# Atom_Multiout_Main.net
KiCad netlist of a schematic drawn in EAGLE
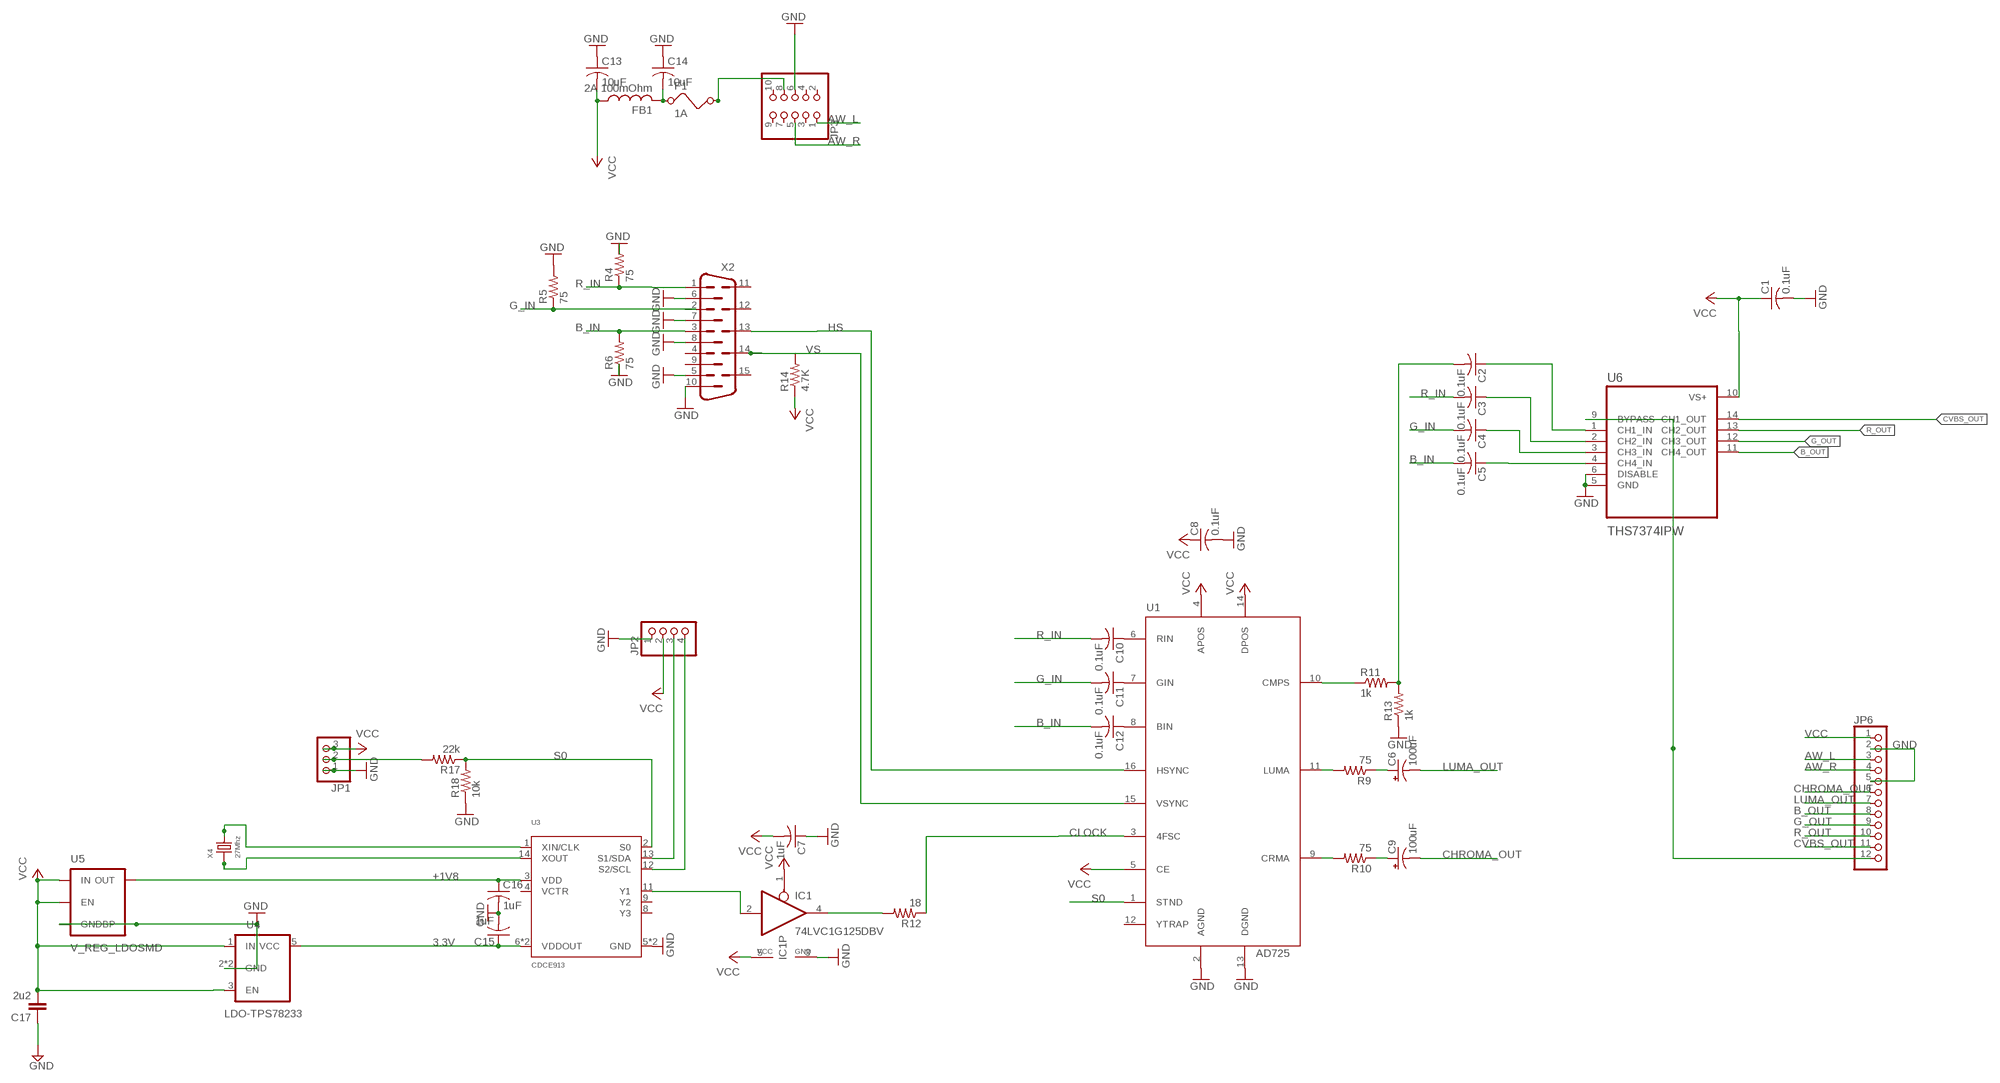
[diagram p0: schematic, sheet 1]

(export (version "E")
  (design (tool "Eeschema 10.0.6"))
  (components
    (comp (ref "C1")
      (value "0.1uF")
      (footprint "eagle-import:C0603@1")
      (libsource (lib "eagle-import") (part "C-USC0603"))
    )
    (comp (ref "C2")
      (value "0.1uF")
      (footprint "eagle-import:C0603@1")
      (libsource (lib "eagle-import") (part "C-USC0603"))
    )
    (comp (ref "C3")
      (value "0.1uF")
      (footprint "eagle-import:C0603@1")
      (libsource (lib "eagle-import") (part "C-USC0603"))
    )
    (comp (ref "C4")
      (value "0.1uF")
      (footprint "eagle-import:C0603@1")
      (libsource (lib "eagle-import") (part "C-USC0603"))
    )
    (comp (ref "C5")
      (value "0.1uF")
      (footprint "eagle-import:C0603@1")
      (libsource (lib "eagle-import") (part "C-USC0603"))
    )
    (comp (ref "C6")
      (value "100uF")
      (footprint "eagle-import:C_6032-28R")
      (libsource (lib "eagle-import") (part "CPOL-USC/6032-28R"))
    )
    (comp (ref "C7")
      (value "1uF")
      (footprint "eagle-import:C0603@1")
      (libsource (lib "eagle-import") (part "C-USC0603"))
    )
    (comp (ref "C8")
      (value "0.1uF")
      (footprint "eagle-import:C0603@1")
      (libsource (lib "eagle-import") (part "C-USC0603"))
    )
    (comp (ref "C9")
      (value "100uF")
      (footprint "eagle-import:C_6032-28R")
      (libsource (lib "eagle-import") (part "CPOL-USC/6032-28R"))
    )
    (comp (ref "C10")
      (value "0.1uF")
      (footprint "eagle-import:C0603@1")
      (libsource (lib "eagle-import") (part "C-USC0603"))
    )
    (comp (ref "C11")
      (value "0.1uF")
      (footprint "eagle-import:C0603@1")
      (libsource (lib "eagle-import") (part "C-USC0603"))
    )
    (comp (ref "C12")
      (value "0.1uF")
      (footprint "eagle-import:C0603@1")
      (libsource (lib "eagle-import") (part "C-USC0603"))
    )
    (comp (ref "C13")
      (value "10uF")
      (footprint "eagle-import:C0603@1")
      (libsource (lib "eagle-import") (part "C-USC0603"))
    )
    (comp (ref "C14")
      (value "10uF")
      (footprint "eagle-import:C0603@1")
      (libsource (lib "eagle-import") (part "C-USC0603"))
    )
    (comp (ref "C15")
      (value "1uF")
      (footprint "eagle-import:C0603@1")
      (libsource (lib "eagle-import") (part "C-USC0603"))
    )
    (comp (ref "C16")
      (value "1uF")
      (footprint "eagle-import:C0603@1")
      (libsource (lib "eagle-import") (part "C-USC0603"))
    )
    (comp (ref "C17")
      (value "2u2")
      (footprint "eagle-import:C0603")
      (libsource (lib "eagle-import") (part "C-EUC0603"))
    )
    (comp (ref "F1")
      (value "1A")
      (footprint "eagle-import:1812")
      (libsource (lib "eagle-import") (part "FUSEF"))
    )
    (comp (ref "FB1")
      (value "2A 100mOhm")
      (footprint "eagle-import:0805")
      (libsource (lib "eagle-import") (part "FERRITE-BEADB"))
    )
    (comp (ref "IC1")
      (value "74LVC1G125DBV")
      (footprint "eagle-import:SOT23-5")
      (libsource (lib "eagle-import") (part "741G125DBVLVC"))
    )
    (comp (ref "JP1")
      (value "PINHD-1X03_2.54-S")
      (footprint "eagle-import:1X03-S")
      (libsource (lib "eagle-import") (part "PINHD-1X03_2.54-S"))
    )
    (comp (ref "JP2")
      (value "PINHD-1X04_2.00")
      (footprint "eagle-import:1X04M")
      (libsource (lib "eagle-import") (part "PINHD-1X04_2.00"))
    )
    (comp (ref "JP3")
      (value "PINHD-2X05_2.00")
      (footprint "eagle-import:2X05M")
      (libsource (lib "eagle-import") (part "PINHD-2X05_2.00"))
    )
    (comp (ref "JP6")
      (value "PINHD-1X12_2.54-S")
      (footprint "eagle-import:1X12-S")
      (libsource (lib "eagle-import") (part "PINHD-1X12_2.54-S"))
    )
    (comp (ref "R4")
      (value "75")
      (footprint "eagle-import:R0603")
      (libsource (lib "eagle-import") (part "R-US_R0603"))
    )
    (comp (ref "R5")
      (value "75")
      (footprint "eagle-import:R0603")
      (libsource (lib "eagle-import") (part "R-US_R0603"))
    )
    (comp (ref "R6")
      (value "75")
      (footprint "eagle-import:R0603")
      (libsource (lib "eagle-import") (part "R-US_R0603"))
    )
    (comp (ref "R9")
      (value "75")
      (footprint "eagle-import:R0603")
      (libsource (lib "eagle-import") (part "R-US_R0603"))
    )
    (comp (ref "R10")
      (value "75")
      (footprint "eagle-import:R0603")
      (libsource (lib "eagle-import") (part "R-US_R0603"))
    )
    (comp (ref "R11")
      (value "1k")
      (footprint "eagle-import:R0603")
      (libsource (lib "eagle-import") (part "R-US_R0603"))
    )
    (comp (ref "R12")
      (value "18")
      (footprint "eagle-import:R0603")
      (libsource (lib "eagle-import") (part "R-US_R0603"))
    )
    (comp (ref "R13")
      (value "1k")
      (footprint "eagle-import:R0603")
      (libsource (lib "eagle-import") (part "R-US_R0603"))
    )
    (comp (ref "R14")
      (value "4.7K")
      (footprint "eagle-import:R0603")
      (libsource (lib "eagle-import") (part "R-US_R0603"))
    )
    (comp (ref "R17")
      (value "22k")
      (footprint "eagle-import:R0603")
      (libsource (lib "eagle-import") (part "R-US_R0603"))
    )
    (comp (ref "R18")
      (value "10k")
      (footprint "eagle-import:R0603")
      (libsource (lib "eagle-import") (part "R-US_R0603"))
    )
    (comp (ref "U1")
      (value "AD725")
      (footprint "eagle-import:SOIC16W")
      (libsource (lib "eagle-import") (part "AD725"))
    )
    (comp (ref "U3")
      (value "CDCE913")
      (footprint "eagle-import:TSSOP14")
      (libsource (lib "eagle-import") (part "CDCE913"))
    )
    (comp (ref "U4")
      (value "LDO-TPS78233")
      (footprint "eagle-import:SOT23-5")
      (libsource (lib "eagle-import") (part "LDO-TPS78233"))
    )
    (comp (ref "U5")
      (value "V_REG_LDOSMD")
      (footprint "eagle-import:SOT23-5")
      (libsource (lib "eagle-import") (part "V_REG_LDOSMD"))
    )
    (comp (ref "U6")
      (value "THS7374IPW")
      (footprint "eagle-import:SOP65P640X120-14N")
      (fields (field (name "MF") "Texas Instruments"))
      (libsource (lib "eagle-import") (part "THS7374IPW"))
    )
    (comp (ref "X2")
      (value "HM15V")
      (footprint "eagle-import:HDM15V")
      (libsource (lib "eagle-import") (part "HM15V"))
    )
    (comp (ref "X4")
      (value "27Mhz")
      (footprint "eagle-import:X2-SMD-5.0X3.2X1.3MM")
      (libsource (lib "eagle-import") (part "CRYSTAL'5032'"))
    )
  )
  (nets
    (net (code "1") (name "/+1V8") (class "Default")
      (node (ref "C16") (pin "1") (pinfunction "1_1") (pintype "passive"))
      (node (ref "U3") (pin "3") (pinfunction "VDD_3") (pintype "bidirectional"))
      (node (ref "U5") (pin "5") (pinfunction "OUT_5") (pintype "passive"))
    )
    (net (code "2") (name "/3.3V") (class "Default")
      (node (ref "C15") (pin "1") (pinfunction "1_1") (pintype "passive"))
      (node (ref "U3") (pin "6") (pinfunction "VDDOUT_6") (pintype "bidirectional"))
      (node (ref "U3") (pin "7") (pinfunction "VDDOUT_7") (pintype "bidirectional"))
      (node (ref "U4") (pin "5") (pinfunction "VCC_5") (pintype "power_in"))
    )
    (net (code "3") (name "/AW_L") (class "Default")
      (node (ref "JP3") (pin "1") (pinfunction "1_1") (pintype "passive"))
      (node (ref "JP6") (pin "3") (pinfunction "3_3") (pintype "passive"))
    )
    (net (code "4") (name "/AW_R") (class "Default")
      (node (ref "JP3") (pin "5") (pinfunction "5_5") (pintype "passive"))
      (node (ref "JP6") (pin "4") (pinfunction "4_4") (pintype "passive"))
    )
    (net (code "5") (name "/B_IN") (class "Default")
      (node (ref "C12") (pin "2") (pinfunction "2_2") (pintype "passive"))
      (node (ref "C5") (pin "2") (pinfunction "2_2") (pintype "passive"))
      (node (ref "R6") (pin "2") (pinfunction "2_2") (pintype "passive"))
      (node (ref "X2") (pin "3") (pinfunction "3_3") (pintype "passive"))
    )
    (net (code "6") (name "/CHROMA_OUT") (class "Default")
      (node (ref "C9") (pin "-") (pinfunction "-_-") (pintype "passive"))
      (node (ref "JP6") (pin "6") (pinfunction "6_6") (pintype "passive"))
    )
    (net (code "7") (name "/CLOCK") (class "Default")
      (node (ref "R12") (pin "1") (pinfunction "1_1") (pintype "passive"))
      (node (ref "U1") (pin "3") (pinfunction "4FSC_3") (pintype "input"))
    )
    (net (code "8") (name "/G_IN") (class "Default")
      (node (ref "C11") (pin "2") (pinfunction "2_2") (pintype "passive"))
      (node (ref "C4") (pin "2") (pinfunction "2_2") (pintype "passive"))
      (node (ref "R5") (pin "1") (pinfunction "1_1") (pintype "passive"))
      (node (ref "X2") (pin "2") (pinfunction "2_2") (pintype "passive"))
    )
    (net (code "9") (name "/HS") (class "Default")
      (node (ref "U1") (pin "16") (pinfunction "HSYNC_16") (pintype "input"))
      (node (ref "X2") (pin "13") (pinfunction "13_13") (pintype "passive"))
    )
    (net (code "10") (name "/LUMA_OUT") (class "Default")
      (node (ref "C6") (pin "-") (pinfunction "-_-") (pintype "passive"))
      (node (ref "JP6") (pin "7") (pinfunction "7_7") (pintype "passive"))
    )
    (net (code "11") (name "/R_IN") (class "Default")
      (node (ref "C10") (pin "2") (pinfunction "2_2") (pintype "passive"))
      (node (ref "C3") (pin "2") (pinfunction "2_2") (pintype "passive"))
      (node (ref "R4") (pin "1") (pinfunction "1_1") (pintype "passive"))
      (node (ref "X2") (pin "1") (pinfunction "1_1") (pintype "passive"))
    )
    (net (code "12") (name "/S0") (class "Default")
      (node (ref "R17") (pin "1") (pinfunction "1_1") (pintype "passive"))
      (node (ref "R18") (pin "2") (pinfunction "2_2") (pintype "passive"))
      (node (ref "U1") (pin "1") (pinfunction "STND_1") (pintype "input"))
      (node (ref "U3") (pin "2") (pinfunction "S0_2") (pintype "bidirectional"))
    )
    (net (code "13") (name "/VS") (class "Default")
      (node (ref "R14") (pin "2") (pinfunction "2_2") (pintype "passive"))
      (node (ref "U1") (pin "15") (pinfunction "VSYNC_15") (pintype "input"))
      (node (ref "X2") (pin "14") (pinfunction "14_14") (pintype "passive"))
    )
    (net (code "14") (name "B_OUT") (class "Default")
      (node (ref "JP6") (pin "8") (pinfunction "8_8") (pintype "passive"))
      (node (ref "U6") (pin "11") (pinfunction "CH4_OUT_11") (pintype "output"))
    )
    (net (code "15") (name "CVBS_OUT") (class "Default")
      (node (ref "JP6") (pin "11") (pinfunction "11_11") (pintype "passive"))
      (node (ref "U6") (pin "14") (pinfunction "CH1_OUT_14") (pintype "output"))
    )
    (net (code "16") (name "GND") (class "Default")
      (node (ref "C1") (pin "2") (pinfunction "2_2") (pintype "passive"))
      (node (ref "C13") (pin "1") (pinfunction "1_1") (pintype "passive"))
      (node (ref "C14") (pin "1") (pinfunction "1_1") (pintype "passive"))
      (node (ref "C15") (pin "2") (pinfunction "2_2") (pintype "passive"))
      (node (ref "C16") (pin "2") (pinfunction "2_2") (pintype "passive"))
      (node (ref "C17") (pin "1") (pinfunction "1_1") (pintype "passive"))
      (node (ref "C7") (pin "1") (pinfunction "1_1") (pintype "passive"))
      (node (ref "C8") (pin "2") (pinfunction "2_2") (pintype "passive"))
      (node (ref "IC1") (pin "3") (pinfunction "GND_3") (pintype "power_in"))
      (node (ref "JP1") (pin "1") (pinfunction "1_1") (pintype "passive"))
      (node (ref "JP2") (pin "1") (pinfunction "1_1") (pintype "passive"))
      (node (ref "JP3") (pin "6") (pinfunction "6_6") (pintype "passive"))
      (node (ref "JP6") (pin "2") (pinfunction "2_2") (pintype "passive"))
      (node (ref "JP6") (pin "5") (pinfunction "5_5") (pintype "passive"))
      (node (ref "R13") (pin "1") (pinfunction "1_1") (pintype "passive"))
      (node (ref "R18") (pin "1") (pinfunction "1_1") (pintype "passive"))
      (node (ref "R4") (pin "2") (pinfunction "2_2") (pintype "passive"))
      (node (ref "R5") (pin "2") (pinfunction "2_2") (pintype "passive"))
      (node (ref "R6") (pin "1") (pinfunction "1_1") (pintype "passive"))
      (node (ref "U1") (pin "13") (pinfunction "DGND_13") (pintype "power_in"))
      (node (ref "U1") (pin "2") (pinfunction "AGND_2") (pintype "power_in"))
      (node (ref "U3") (pin "10") (pinfunction "GND_10") (pintype "bidirectional"))
      (node (ref "U3") (pin "5") (pinfunction "GND_5") (pintype "bidirectional"))
      (node (ref "U4") (pin "2") (pinfunction "GND_2") (pintype "input"))
      (node (ref "U4") (pin "4") (pinfunction "GND_4") (pintype "input"))
      (node (ref "U5") (pin "2") (pinfunction "GND_2") (pintype "input"))
      (node (ref "U5") (pin "4") (pinfunction "BP_4") (pintype "input"))
      (node (ref "U6") (pin "5") (pinfunction "GND_5") (pintype "input"))
      (node (ref "U6") (pin "6") (pinfunction "DISABLE_6") (pintype "input"))
      (node (ref "X2") (pin "10") (pinfunction "10_10") (pintype "passive"))
      (node (ref "X2") (pin "5") (pinfunction "5_5") (pintype "passive"))
      (node (ref "X2") (pin "6") (pinfunction "6_6") (pintype "passive"))
      (node (ref "X2") (pin "7") (pinfunction "7_7") (pintype "passive"))
      (node (ref "X2") (pin "8") (pinfunction "8_8") (pintype "passive"))
    )
    (net (code "17") (name "G_OUT") (class "Default")
      (node (ref "JP6") (pin "9") (pinfunction "9_9") (pintype "passive"))
      (node (ref "U6") (pin "12") (pinfunction "CH3_OUT_12") (pintype "output"))
    )
    (net (code "18") (name "Net-(C2-Pad2)") (class "Default")
      (node (ref "C2") (pin "2") (pinfunction "2_2") (pintype "passive"))
      (node (ref "R11") (pin "2") (pinfunction "2_2") (pintype "passive"))
      (node (ref "R13") (pin "2") (pinfunction "2_2") (pintype "passive"))
    )
    (net (code "19") (name "Net-(C6-Pad+)") (class "Default")
      (node (ref "C6") (pin "+") (pinfunction "+_+") (pintype "passive"))
      (node (ref "R9") (pin "1") (pinfunction "1_1") (pintype "passive"))
    )
    (net (code "20") (name "Net-(C9-Pad+)") (class "Default")
      (node (ref "C9") (pin "+") (pinfunction "+_+") (pintype "passive"))
      (node (ref "R10") (pin "1") (pinfunction "1_1") (pintype "passive"))
    )
    (net (code "21") (name "Net-(C14-Pad2)") (class "Default")
      (node (ref "C14") (pin "2") (pinfunction "2_2") (pintype "passive"))
      (node (ref "F1") (pin "1") (pinfunction "1_1") (pintype "passive"))
      (node (ref "FB1") (pin "2") (pinfunction "2_2") (pintype "passive"))
    )
    (net (code "22") (name "Net-(F1-Pad2)") (class "Default")
      (node (ref "F1") (pin "2") (pinfunction "2_2") (pintype "passive"))
      (node (ref "JP3") (pin "8") (pinfunction "8_8") (pintype "passive"))
    )
    (net (code "23") (name "Net-(IC1A-I)") (class "Default")
      (node (ref "IC1") (pin "2") (pinfunction "I_2") (pintype "input"))
      (node (ref "U3") (pin "11") (pinfunction "Y1_11") (pintype "bidirectional"))
    )
    (net (code "24") (name "Net-(IC1A-O)") (class "Default")
      (node (ref "IC1") (pin "4") (pinfunction "O_4") (pintype "tri_state"))
      (node (ref "R12") (pin "2") (pinfunction "2_2") (pintype "passive"))
    )
    (net (code "25") (name "Net-(JP1-Pad2)") (class "Default")
      (node (ref "JP1") (pin "2") (pinfunction "2_2") (pintype "passive"))
      (node (ref "R17") (pin "2") (pinfunction "2_2") (pintype "passive"))
    )
    (net (code "26") (name "Net-(U1-BIN)") (class "Default")
      (node (ref "C12") (pin "1") (pinfunction "1_1") (pintype "passive"))
      (node (ref "U1") (pin "8") (pinfunction "BIN_8") (pintype "input"))
    )
    (net (code "27") (name "Net-(U1-CMPS)") (class "Default")
      (node (ref "R11") (pin "1") (pinfunction "1_1") (pintype "passive"))
      (node (ref "U1") (pin "10") (pinfunction "CMPS_10") (pintype "output"))
    )
    (net (code "28") (name "Net-(U1-CRMA)") (class "Default")
      (node (ref "R10") (pin "2") (pinfunction "2_2") (pintype "passive"))
      (node (ref "U1") (pin "9") (pinfunction "CRMA_9") (pintype "output"))
    )
    (net (code "29") (name "Net-(U1-GIN)") (class "Default")
      (node (ref "C11") (pin "1") (pinfunction "1_1") (pintype "passive"))
      (node (ref "U1") (pin "7") (pinfunction "GIN_7") (pintype "input"))
    )
    (net (code "30") (name "Net-(U1-LUMA)") (class "Default")
      (node (ref "R9") (pin "2") (pinfunction "2_2") (pintype "passive"))
      (node (ref "U1") (pin "11") (pinfunction "LUMA_11") (pintype "output"))
    )
    (net (code "31") (name "Net-(U1-RIN)") (class "Default")
      (node (ref "C10") (pin "1") (pinfunction "1_1") (pintype "passive"))
      (node (ref "U1") (pin "6") (pinfunction "RIN_6") (pintype "input"))
    )
    (net (code "32") (name "Net-(U3-S1{slash}SDA)") (class "Default")
      (node (ref "JP2") (pin "3") (pinfunction "3_3") (pintype "passive"))
      (node (ref "U3") (pin "13") (pinfunction "S1/SDA_13") (pintype "bidirectional"))
    )
    (net (code "33") (name "Net-(U3-S2{slash}SCL)") (class "Default")
      (node (ref "JP2") (pin "4") (pinfunction "4_4") (pintype "passive"))
      (node (ref "U3") (pin "12") (pinfunction "S2/SCL_12") (pintype "bidirectional"))
    )
    (net (code "34") (name "Net-(U3-XIN{slash}CLK)") (class "Default")
      (node (ref "U3") (pin "1") (pinfunction "XIN/CLK_1") (pintype "bidirectional"))
      (node (ref "X4") (pin "2") (pinfunction "2_2") (pintype "passive"))
    )
    (net (code "35") (name "Net-(U3-XOUT)") (class "Default")
      (node (ref "U3") (pin "14") (pinfunction "XOUT_14") (pintype "bidirectional"))
      (node (ref "X4") (pin "1") (pinfunction "1_1") (pintype "passive"))
    )
    (net (code "36") (name "Net-(U6-BYPASS)") (class "Default")
      (node (ref "JP6") (pin "12") (pinfunction "12_12") (pintype "passive"))
      (node (ref "U6") (pin "9") (pinfunction "BYPASS_9") (pintype "input"))
    )
    (net (code "37") (name "Net-(U6-CH1_IN)") (class "Default")
      (node (ref "C2") (pin "1") (pinfunction "1_1") (pintype "passive"))
      (node (ref "U6") (pin "1") (pinfunction "CH1_IN_1") (pintype "input"))
    )
    (net (code "38") (name "Net-(U6-CH2_IN)") (class "Default")
      (node (ref "C3") (pin "1") (pinfunction "1_1") (pintype "passive"))
      (node (ref "U6") (pin "2") (pinfunction "CH2_IN_2") (pintype "input"))
    )
    (net (code "39") (name "Net-(U6-CH3_IN)") (class "Default")
      (node (ref "C4") (pin "1") (pinfunction "1_1") (pintype "passive"))
      (node (ref "U6") (pin "3") (pinfunction "CH3_IN_3") (pintype "input"))
    )
    (net (code "40") (name "Net-(U6-CH4_IN)") (class "Default")
      (node (ref "C5") (pin "1") (pinfunction "1_1") (pintype "passive"))
      (node (ref "U6") (pin "4") (pinfunction "CH4_IN_4") (pintype "input"))
    )
    (net (code "41") (name "R_OUT") (class "Default")
      (node (ref "JP6") (pin "10") (pinfunction "10_10") (pintype "passive"))
      (node (ref "U6") (pin "13") (pinfunction "CH2_OUT_13") (pintype "output"))
    )
    (net (code "42") (name "VCC") (class "Default")
      (node (ref "C1") (pin "1") (pinfunction "1_1") (pintype "passive"))
      (node (ref "C13") (pin "2") (pinfunction "2_2") (pintype "passive"))
      (node (ref "C17") (pin "2") (pinfunction "2_2") (pintype "passive"))
      (node (ref "C7") (pin "2") (pinfunction "2_2") (pintype "passive"))
      (node (ref "C8") (pin "1") (pinfunction "1_1") (pintype "passive"))
      (node (ref "FB1") (pin "1") (pinfunction "1_1") (pintype "passive"))
      (node (ref "IC1") (pin "1") (pinfunction "OE_1") (pintype "input"))
      (node (ref "IC1") (pin "5") (pinfunction "VCC_5") (pintype "power_in"))
      (node (ref "JP1") (pin "3") (pinfunction "3_3") (pintype "passive"))
      (node (ref "JP2") (pin "2") (pinfunction "2_2") (pintype "passive"))
      (node (ref "JP6") (pin "1") (pinfunction "1_1") (pintype "passive"))
      (node (ref "R14") (pin "1") (pinfunction "1_1") (pintype "passive"))
      (node (ref "U1") (pin "14") (pinfunction "DPOS_14") (pintype "power_in"))
      (node (ref "U1") (pin "4") (pinfunction "APOS_4") (pintype "power_in"))
      (node (ref "U1") (pin "5") (pinfunction "CE_5") (pintype "input"))
      (node (ref "U4") (pin "1") (pinfunction "IN_1") (pintype "input"))
      (node (ref "U4") (pin "3") (pinfunction "EN_3") (pintype "input"))
      (node (ref "U5") (pin "1") (pinfunction "IN_1") (pintype "input"))
      (node (ref "U5") (pin "3") (pinfunction "EN_3") (pintype "input"))
      (node (ref "U6") (pin "10") (pinfunction "VS+_10") (pintype "power_in"))
    )
    (net (code "43") (name "unconnected-(JP3-Pad2)") (class "Default")
      (node (ref "JP3") (pin "2") (pinfunction "2_2") (pintype "passive"))
    )
    (net (code "44") (name "unconnected-(JP3-Pad3)") (class "Default")
      (node (ref "JP3") (pin "3") (pinfunction "3_3") (pintype "passive"))
    )
    (net (code "45") (name "unconnected-(JP3-Pad4)") (class "Default")
      (node (ref "JP3") (pin "4") (pinfunction "4_4") (pintype "passive"))
    )
    (net (code "46") (name "unconnected-(JP3-Pad7)") (class "Default")
      (node (ref "JP3") (pin "7") (pinfunction "7_7") (pintype "passive"))
    )
    (net (code "47") (name "unconnected-(JP3-Pad9)") (class "Default")
      (node (ref "JP3") (pin "9") (pinfunction "9_9") (pintype "passive"))
    )
    (net (code "48") (name "unconnected-(JP3-Pad10)") (class "Default")
      (node (ref "JP3") (pin "10") (pinfunction "10_10") (pintype "passive"))
    )
    (net (code "49") (name "unconnected-(U1-YTRAP-Pad12)") (class "Default")
      (node (ref "U1") (pin "12") (pinfunction "YTRAP_12") (pintype "output"))
    )
    (net (code "50") (name "unconnected-(U3-VCTR-Pad4)") (class "Default")
      (node (ref "U3") (pin "4") (pinfunction "VCTR_4") (pintype "bidirectional"))
    )
    (net (code "51") (name "unconnected-(U3-Y2-Pad9)") (class "Default")
      (node (ref "U3") (pin "9") (pinfunction "Y2_9") (pintype "bidirectional"))
    )
    (net (code "52") (name "unconnected-(U3-Y3-Pad8)") (class "Default")
      (node (ref "U3") (pin "8") (pinfunction "Y3_8") (pintype "bidirectional"))
    )
    (net (code "53") (name "unconnected-(X2-Pad4)") (class "Default")
      (node (ref "X2") (pin "4") (pinfunction "4_4") (pintype "passive"))
    )
    (net (code "54") (name "unconnected-(X2-Pad9)") (class "Default")
      (node (ref "X2") (pin "9") (pinfunction "9_9") (pintype "passive"))
    )
    (net (code "55") (name "unconnected-(X2-Pad11)") (class "Default")
      (node (ref "X2") (pin "11") (pinfunction "11_11") (pintype "passive"))
    )
    (net (code "56") (name "unconnected-(X2-Pad12)") (class "Default")
      (node (ref "X2") (pin "12") (pinfunction "12_12") (pintype "passive"))
    )
    (net (code "57") (name "unconnected-(X2-Pad15)") (class "Default")
      (node (ref "X2") (pin "15") (pinfunction "15_15") (pintype "passive"))
    )
  )
)
